# PSocC_Motor_Driver_Design_1.net
KiCad netlist of a schematic drawn in EAGLE
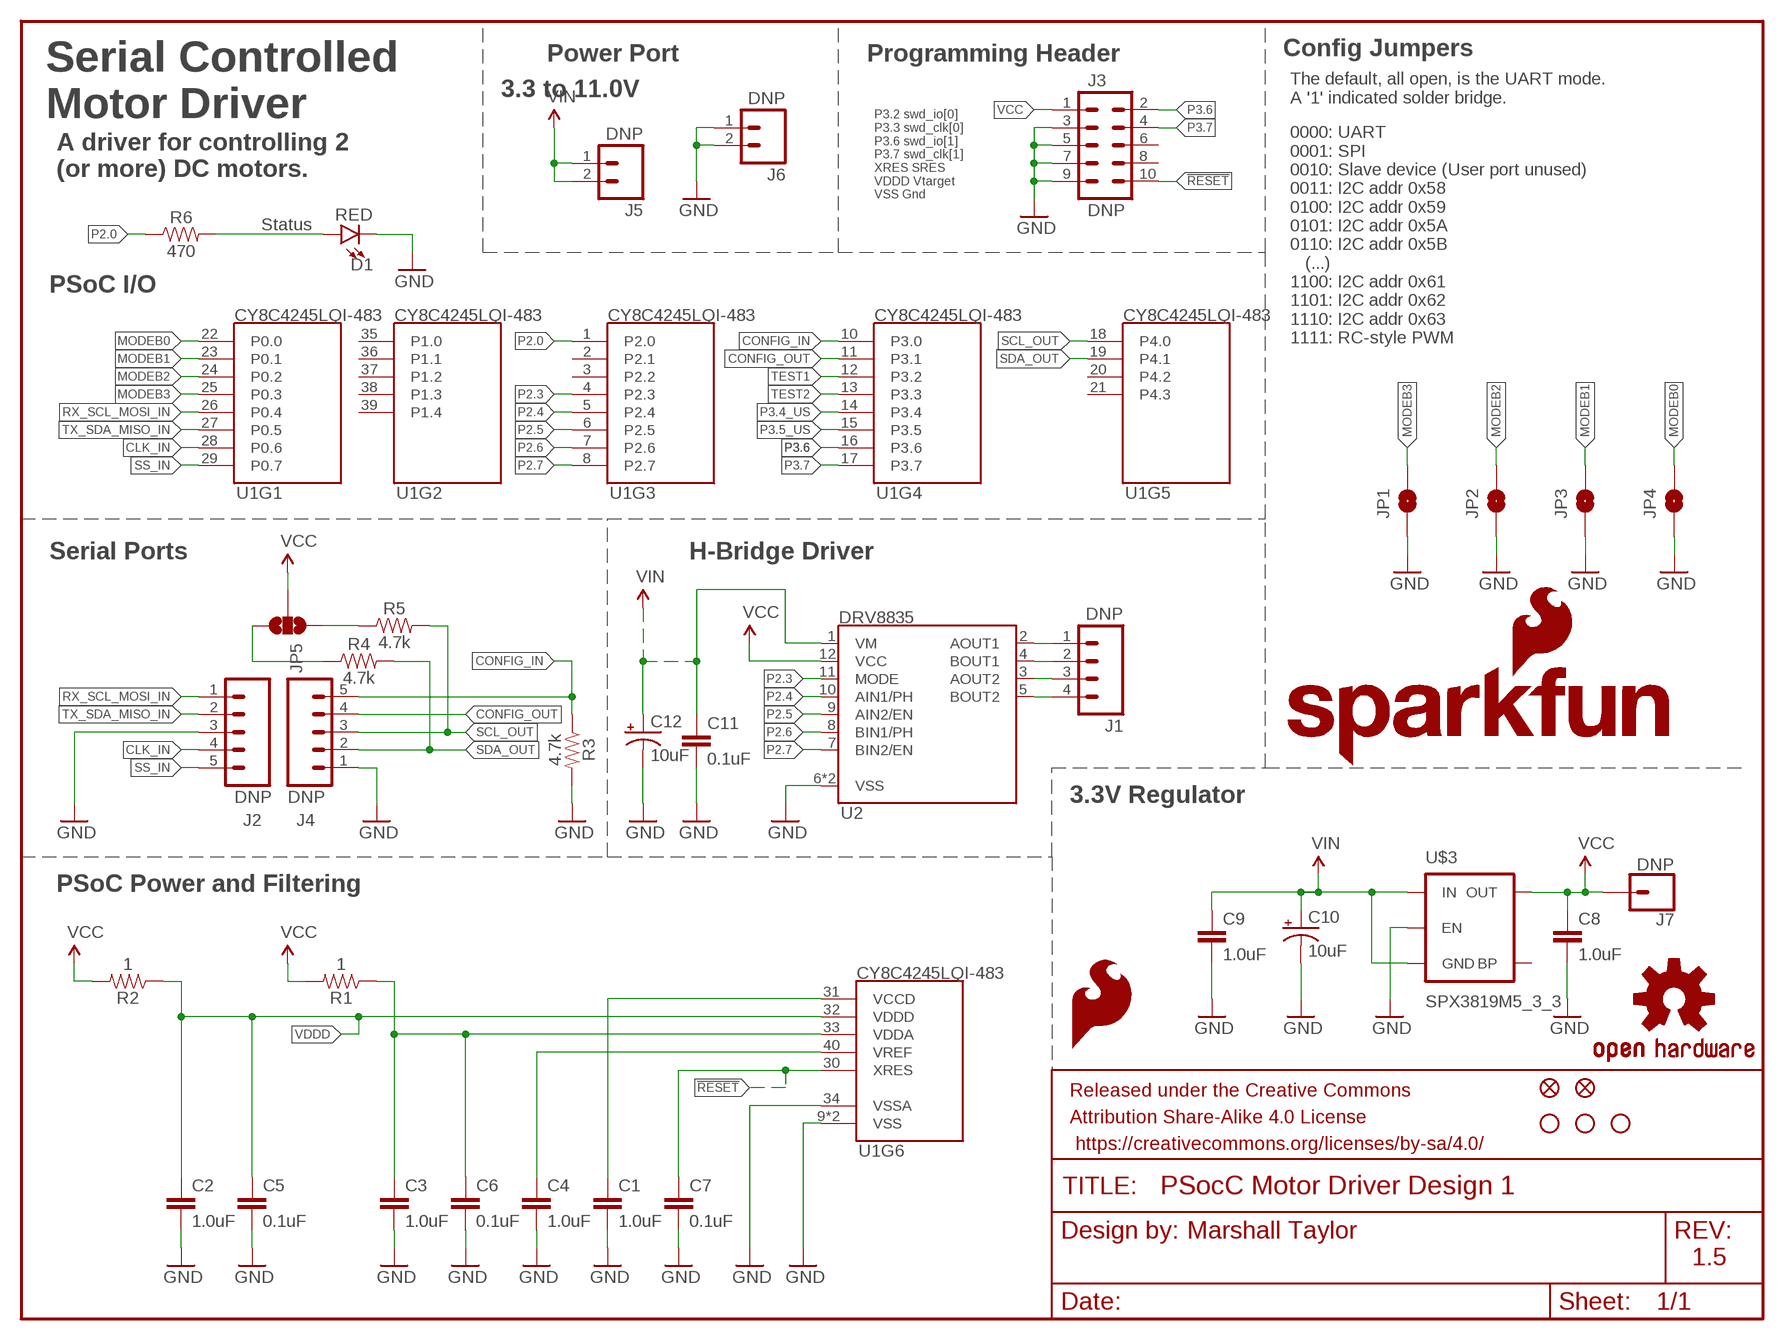
[diagram p0: schematic, sheet 1]

(export (version "E")
  (design (tool "Eeschema 10.0.6"))
  (components
    (comp (ref "C1")
      (value "1.0uF")
      (footprint "eagle-import:0402")
      (libsource (lib "eagle-import") (part "1.0UF-0402-16V-10%"))
    )
    (comp (ref "C2")
      (value "1.0uF")
      (footprint "eagle-import:0402")
      (libsource (lib "eagle-import") (part "1.0UF-0402-16V-10%"))
    )
    (comp (ref "C3")
      (value "1.0uF")
      (footprint "eagle-import:0402")
      (libsource (lib "eagle-import") (part "1.0UF-0402-16V-10%"))
    )
    (comp (ref "C4")
      (value "1.0uF")
      (footprint "eagle-import:0402")
      (libsource (lib "eagle-import") (part "1.0UF-0402-16V-10%"))
    )
    (comp (ref "C5")
      (value "0.1uF")
      (footprint "eagle-import:0402")
      (libsource (lib "eagle-import") (part "0.1UF-0402-16V-10%"))
    )
    (comp (ref "C6")
      (value "0.1uF")
      (footprint "eagle-import:0402")
      (libsource (lib "eagle-import") (part "0.1UF-0402-16V-10%"))
    )
    (comp (ref "C7")
      (value "0.1uF")
      (footprint "eagle-import:0402")
      (libsource (lib "eagle-import") (part "0.1UF-0402-16V-10%"))
    )
    (comp (ref "C8")
      (value "1.0uF")
      (footprint "eagle-import:0402")
      (libsource (lib "eagle-import") (part "1.0UF-0402-16V-10%"))
    )
    (comp (ref "C9")
      (value "1.0uF")
      (footprint "eagle-import:0402")
      (libsource (lib "eagle-import") (part "1.0UF-0402-16V-10%"))
    )
    (comp (ref "C10")
      (value "10uF")
      (footprint "eagle-import:EIA3216")
      (libsource (lib "eagle-import") (part "10UF-POLAR-EIA3216-16V-10%(TANT)"))
    )
    (comp (ref "C11")
      (value "0.1uF")
      (footprint "eagle-import:0402")
      (libsource (lib "eagle-import") (part "0.1UF-0402-16V-10%"))
    )
    (comp (ref "C12")
      (value "10uF")
      (footprint "eagle-import:EIA3216")
      (libsource (lib "eagle-import") (part "10UF-POLAR-EIA3216-16V-10%(TANT)"))
    )
    (comp (ref "D1")
      (value "RED")
      (footprint "eagle-import:LED-0603")
      (libsource (lib "eagle-import") (part "LED-RED0603"))
    )
    (comp (ref "FD1")
      (value "FIDUCIALUFIDUCIAL")
      (footprint "eagle-import:MICRO-FIDUCIAL")
      (libsource (lib "eagle-import") (part "FIDUCIALUFIDUCIAL"))
    )
    (comp (ref "FD2")
      (value "FIDUCIALUFIDUCIAL")
      (footprint "eagle-import:MICRO-FIDUCIAL")
      (libsource (lib "eagle-import") (part "FIDUCIALUFIDUCIAL"))
    )
    (comp (ref "FRAME1")
      (value "FRAME-LETTER")
      (footprint "eagle-import:CREATIVE_COMMONS")
      (libsource (lib "eagle-import") (part "FRAME-LETTER"))
    )
    (comp (ref "H1")
      (value "STAND-OFF")
      (footprint "eagle-import:STAND-OFF")
      (libsource (lib "eagle-import") (part "STAND-OFF"))
    )
    (comp (ref "H2")
      (value "STAND-OFF")
      (footprint "eagle-import:STAND-OFF")
      (libsource (lib "eagle-import") (part "STAND-OFF"))
    )
    (comp (ref "H3")
      (value "STAND-OFF")
      (footprint "eagle-import:STAND-OFF")
      (libsource (lib "eagle-import") (part "STAND-OFF"))
    )
    (comp (ref "J1")
      (value "DNP")
      (footprint "eagle-import:1X04")
      (libsource (lib "eagle-import") (part "M04PTH"))
    )
    (comp (ref "J2")
      (value "DNP")
      (footprint "eagle-import:1X05")
      (libsource (lib "eagle-import") (part "M05PTH"))
    )
    (comp (ref "J3")
      (value "DNP")
      (footprint "eagle-import:2X5_PTH_SILK_.05")
      (libsource (lib "eagle-import") (part "M05X20.05_IN_PTH_SILK"))
    )
    (comp (ref "J4")
      (value "DNP")
      (footprint "eagle-import:1X05")
      (libsource (lib "eagle-import") (part "M05PTH"))
    )
    (comp (ref "J5")
      (value "DNP")
      (footprint "eagle-import:1X02")
      (libsource (lib "eagle-import") (part "M02PTH"))
    )
    (comp (ref "J6")
      (value "DNP")
      (footprint "eagle-import:1X02")
      (libsource (lib "eagle-import") (part "M02PTH"))
    )
    (comp (ref "J7")
      (value "DNP")
      (footprint "eagle-import:1X01")
      (libsource (lib "eagle-import") (part "CONN_01PTH"))
    )
    (comp (ref "JP1")
      (value "JUMPER-PAD-2")
      (footprint "eagle-import:PAD-JUMPER-2-NO_YES_SILK")
      (libsource (lib "eagle-import") (part "JUMPER-PAD-2-NOYES_SILK"))
    )
    (comp (ref "JP2")
      (value "JUMPER-PAD-2")
      (footprint "eagle-import:PAD-JUMPER-2-NO_YES_SILK")
      (libsource (lib "eagle-import") (part "JUMPER-PAD-2-NOYES_SILK"))
    )
    (comp (ref "JP3")
      (value "JUMPER-PAD-2")
      (footprint "eagle-import:PAD-JUMPER-2-NO_YES_SILK")
      (libsource (lib "eagle-import") (part "JUMPER-PAD-2-NOYES_SILK"))
    )
    (comp (ref "JP4")
      (value "JUMPER-PAD-2")
      (footprint "eagle-import:PAD-JUMPER-2-NO_YES_SILK")
      (libsource (lib "eagle-import") (part "JUMPER-PAD-2-NOYES_SILK"))
    )
    (comp (ref "JP5")
      (value "JUMPER-PAD-3-NOYES_SILK")
      (footprint "eagle-import:PAD-JUMPER-3-NO_YES_SILK")
      (libsource (lib "eagle-import") (part "JUMPER-PAD-3-NOYES_SILK"))
    )
    (comp (ref "LOGO1")
      (value "SFE_LOGO_FLAME.1_INCH")
      (footprint "eagle-import:SFE_LOGO_FLAME_.1")
      (libsource (lib "eagle-import") (part "SFE_LOGO_FLAME.1_INCH"))
    )
    (comp (ref "LOGO2")
      (value "OSHW-LOGOMINI")
      (footprint "eagle-import:OSHW-LOGO-MINI")
      (libsource (lib "eagle-import") (part "OSHW-LOGOMINI"))
    )
    (comp (ref "LOGO3")
      (value "SFE_LOGO_NAME_FLAME.1_INCH")
      (footprint "eagle-import:SFE_LOGO_NAME_FLAME_.1")
      (libsource (lib "eagle-import") (part "SFE_LOGO_NAME_FLAME.1_INCH"))
    )
    (comp (ref "R1")
      (value "1")
      (footprint "eagle-import:0603")
      (libsource (lib "eagle-import") (part "1OHM-0603-1/10W-1%"))
    )
    (comp (ref "R2")
      (value "1")
      (footprint "eagle-import:0603")
      (libsource (lib "eagle-import") (part "1OHM-0603-1/10W-1%"))
    )
    (comp (ref "R3")
      (value "4.7k")
      (footprint "eagle-import:0603")
      (libsource (lib "eagle-import") (part "4.7KOHM-0603-1/10W-1%"))
    )
    (comp (ref "R4")
      (value "4.7k")
      (footprint "eagle-import:0603")
      (libsource (lib "eagle-import") (part "4.7KOHM-0603-1/10W-1%"))
    )
    (comp (ref "R5")
      (value "4.7k")
      (footprint "eagle-import:0603")
      (libsource (lib "eagle-import") (part "4.7KOHM-0603-1/10W-1%"))
    )
    (comp (ref "R6")
      (value "470")
      (footprint "eagle-import:0603")
      (libsource (lib "eagle-import") (part "470OHM-0603-1/10W-1%"))
    )
    (comp (ref "U$3")
      (value "SPX3819M5_3_3")
      (footprint "eagle-import:SOT-23-5-VREG")
      (libsource (lib "eagle-import") (part "SPX3819"))
    )
    (comp (ref "U1")
      (value "CY8C4245LQI-483")
      (footprint "eagle-import:QFN-40")
      (libsource (lib "eagle-import") (part "CY8C4245LQI"))
    )
    (comp (ref "U2")
      (value "DRV8835")
      (footprint "eagle-import:WSON-12")
      (fields (field (name "PROD_ID") "IC-13342"))
      (libsource (lib "eagle-import") (part "DRV883X"))
    )
  )
  (nets
    (net (code "1") (name "/~{RESET}") (class "Default")
      (node (ref "C7") (pin "1") (pinfunction "1_1") (pintype "passive"))
      (node (ref "J3") (pin "10") (pinfunction "10_10") (pintype "passive"))
      (node (ref "U1") (pin "30") (pinfunction "XRES_30") (pintype "bidirectional"))
    )
    (net (code "2") (name "CLK_IN") (class "Default")
      (node (ref "J2") (pin "4") (pinfunction "4_4") (pintype "passive"))
      (node (ref "U1") (pin "28") (pinfunction "P0.6_28") (pintype "bidirectional"))
    )
    (net (code "3") (name "CONFIG_IN") (class "Default")
      (node (ref "J4") (pin "5") (pinfunction "5_5") (pintype "passive"))
      (node (ref "R3") (pin "1") (pinfunction "1_1") (pintype "passive"))
      (node (ref "U1") (pin "10") (pinfunction "P3.0_10") (pintype "bidirectional"))
    )
    (net (code "4") (name "CONFIG_OUT") (class "Default")
      (node (ref "J4") (pin "4") (pinfunction "4_4") (pintype "passive"))
      (node (ref "U1") (pin "11") (pinfunction "P3.1_11") (pintype "bidirectional"))
    )
    (net (code "5") (name "GND") (class "Default")
      (node (ref "C1") (pin "2") (pinfunction "2_2") (pintype "passive"))
      (node (ref "C10") (pin "-") (pinfunction "-_-") (pintype "passive"))
      (node (ref "C11") (pin "2") (pinfunction "2_2") (pintype "passive"))
      (node (ref "C12") (pin "-") (pinfunction "-_-") (pintype "passive"))
      (node (ref "C2") (pin "2") (pinfunction "2_2") (pintype "passive"))
      (node (ref "C3") (pin "2") (pinfunction "2_2") (pintype "passive"))
      (node (ref "C4") (pin "2") (pinfunction "2_2") (pintype "passive"))
      (node (ref "C5") (pin "2") (pinfunction "2_2") (pintype "passive"))
      (node (ref "C6") (pin "2") (pinfunction "2_2") (pintype "passive"))
      (node (ref "C7") (pin "2") (pinfunction "2_2") (pintype "passive"))
      (node (ref "C8") (pin "2") (pinfunction "2_2") (pintype "passive"))
      (node (ref "C9") (pin "2") (pinfunction "2_2") (pintype "passive"))
      (node (ref "D1") (pin "C") (pinfunction "C_C") (pintype "passive"))
      (node (ref "J2") (pin "3") (pinfunction "3_3") (pintype "passive"))
      (node (ref "J3") (pin "3") (pinfunction "3_3") (pintype "passive"))
      (node (ref "J3") (pin "5") (pinfunction "5_5") (pintype "passive"))
      (node (ref "J3") (pin "7") (pinfunction "7_7") (pintype "passive"))
      (node (ref "J3") (pin "9") (pinfunction "9_9") (pintype "passive"))
      (node (ref "J4") (pin "1") (pinfunction "1_1") (pintype "passive"))
      (node (ref "J6") (pin "1") (pinfunction "1_1") (pintype "passive"))
      (node (ref "J6") (pin "2") (pinfunction "2_2") (pintype "passive"))
      (node (ref "JP1") (pin "1") (pinfunction "1_1") (pintype "passive"))
      (node (ref "JP2") (pin "1") (pinfunction "1_1") (pintype "passive"))
      (node (ref "JP3") (pin "1") (pinfunction "1_1") (pintype "passive"))
      (node (ref "JP4") (pin "1") (pinfunction "1_1") (pintype "passive"))
      (node (ref "R3") (pin "2") (pinfunction "2_2") (pintype "passive"))
      (node (ref "U$3") (pin "3") (pinfunction "EN_3") (pintype "input"))
      (node (ref "U1") (pin "34") (pinfunction "VSSA_34") (pintype "bidirectional"))
      (node (ref "U1") (pin "9") (pinfunction "VSS_9") (pintype "bidirectional"))
      (node (ref "U1") (pin "EP") (pinfunction "VSS_EP") (pintype "bidirectional"))
      (node (ref "U2") (pin "6") (pinfunction "VSS_6") (pintype "bidirectional"))
      (node (ref "U2") (pin "PAD") (pinfunction "VSS_PAD") (pintype "bidirectional"))
    )
    (net (code "6") (name "MODEB0") (class "Default")
      (node (ref "JP4") (pin "2") (pinfunction "2_2") (pintype "passive"))
      (node (ref "U1") (pin "22") (pinfunction "P0.0_22") (pintype "bidirectional"))
    )
    (net (code "7") (name "MODEB1") (class "Default")
      (node (ref "JP3") (pin "2") (pinfunction "2_2") (pintype "passive"))
      (node (ref "U1") (pin "23") (pinfunction "P0.1_23") (pintype "bidirectional"))
    )
    (net (code "8") (name "MODEB2") (class "Default")
      (node (ref "JP2") (pin "2") (pinfunction "2_2") (pintype "passive"))
      (node (ref "U1") (pin "24") (pinfunction "P0.2_24") (pintype "bidirectional"))
    )
    (net (code "9") (name "MODEB3") (class "Default")
      (node (ref "JP1") (pin "2") (pinfunction "2_2") (pintype "passive"))
      (node (ref "U1") (pin "25") (pinfunction "P0.3_25") (pintype "bidirectional"))
    )
    (net (code "10") (name "Net-(D1-PadA)") (class "Default")
      (node (ref "D1") (pin "A") (pinfunction "A_A") (pintype "passive"))
      (node (ref "R6") (pin "2") (pinfunction "2_2") (pintype "passive"))
    )
    (net (code "11") (name "Net-(JP5-Pad1)") (class "Default")
      (node (ref "JP5") (pin "1") (pinfunction "1_1") (pintype "passive"))
      (node (ref "R5") (pin "1") (pinfunction "1_1") (pintype "passive"))
    )
    (net (code "12") (name "Net-(JP5-Pad3)") (class "Default")
      (node (ref "JP5") (pin "3") (pinfunction "3_3") (pintype "passive"))
      (node (ref "R4") (pin "1") (pinfunction "1_1") (pintype "passive"))
    )
    (net (code "13") (name "Net-(U1F-VCCD)") (class "Default")
      (node (ref "C1") (pin "1") (pinfunction "1_1") (pintype "passive"))
      (node (ref "U1") (pin "31") (pinfunction "VCCD_31") (pintype "bidirectional"))
    )
    (net (code "14") (name "Net-(U1F-VDDA)") (class "Default")
      (node (ref "C3") (pin "1") (pinfunction "1_1") (pintype "passive"))
      (node (ref "C6") (pin "1") (pinfunction "1_1") (pintype "passive"))
      (node (ref "R1") (pin "1") (pinfunction "1_1") (pintype "passive"))
      (node (ref "U1") (pin "33") (pinfunction "VDDA_33") (pintype "bidirectional"))
    )
    (net (code "15") (name "Net-(U1F-VREF)") (class "Default")
      (node (ref "C4") (pin "1") (pinfunction "1_1") (pintype "passive"))
      (node (ref "U1") (pin "40") (pinfunction "VREF_40") (pintype "bidirectional"))
    )
    (net (code "16") (name "Net-(U2-AOUT1)") (class "Default")
      (node (ref "J1") (pin "1") (pinfunction "1_1") (pintype "passive"))
      (node (ref "U2") (pin "2") (pinfunction "AOUT1_2") (pintype "bidirectional"))
    )
    (net (code "17") (name "Net-(U2-AOUT2)") (class "Default")
      (node (ref "J1") (pin "3") (pinfunction "3_3") (pintype "passive"))
      (node (ref "U2") (pin "3") (pinfunction "AOUT2_3") (pintype "bidirectional"))
    )
    (net (code "18") (name "Net-(U2-BOUT1)") (class "Default")
      (node (ref "J1") (pin "2") (pinfunction "2_2") (pintype "passive"))
      (node (ref "U2") (pin "4") (pinfunction "BOUT1_4") (pintype "bidirectional"))
    )
    (net (code "19") (name "Net-(U2-BOUT2)") (class "Default")
      (node (ref "J1") (pin "4") (pinfunction "4_4") (pintype "passive"))
      (node (ref "U2") (pin "5") (pinfunction "BOUT2_5") (pintype "bidirectional"))
    )
    (net (code "20") (name "P2.0") (class "Default")
      (node (ref "R6") (pin "1") (pinfunction "1_1") (pintype "passive"))
      (node (ref "U1") (pin "1") (pinfunction "P2.0_1") (pintype "bidirectional"))
    )
    (net (code "21") (name "P2.3") (class "Default")
      (node (ref "U1") (pin "4") (pinfunction "P2.3_4") (pintype "bidirectional"))
      (node (ref "U2") (pin "11") (pinfunction "MODE_11") (pintype "bidirectional"))
    )
    (net (code "22") (name "P2.4") (class "Default")
      (node (ref "U1") (pin "5") (pinfunction "P2.4_5") (pintype "bidirectional"))
      (node (ref "U2") (pin "10") (pinfunction "AIN1/PH_10") (pintype "bidirectional"))
    )
    (net (code "23") (name "P2.5") (class "Default")
      (node (ref "U1") (pin "6") (pinfunction "P2.5_6") (pintype "bidirectional"))
      (node (ref "U2") (pin "9") (pinfunction "AIN2/EN_9") (pintype "bidirectional"))
    )
    (net (code "24") (name "P2.6") (class "Default")
      (node (ref "U1") (pin "7") (pinfunction "P2.6_7") (pintype "bidirectional"))
      (node (ref "U2") (pin "8") (pinfunction "BIN1/PH_8") (pintype "bidirectional"))
    )
    (net (code "25") (name "P2.7") (class "Default")
      (node (ref "U1") (pin "8") (pinfunction "P2.7_8") (pintype "bidirectional"))
      (node (ref "U2") (pin "7") (pinfunction "BIN2/EN_7") (pintype "bidirectional"))
    )
    (net (code "26") (name "P3.4_US") (class "Default")
      (node (ref "U1") (pin "14") (pinfunction "P3.4_14") (pintype "bidirectional"))
    )
    (net (code "27") (name "P3.5_US") (class "Default")
      (node (ref "U1") (pin "15") (pinfunction "P3.5_15") (pintype "bidirectional"))
    )
    (net (code "28") (name "P3.6") (class "Default")
      (node (ref "J3") (pin "2") (pinfunction "2_2") (pintype "passive"))
      (node (ref "U1") (pin "16") (pinfunction "P3.6_16") (pintype "bidirectional"))
    )
    (net (code "29") (name "P3.7") (class "Default")
      (node (ref "J3") (pin "4") (pinfunction "4_4") (pintype "passive"))
      (node (ref "U1") (pin "17") (pinfunction "P3.7_17") (pintype "bidirectional"))
    )
    (net (code "30") (name "RX_SCL_MOSI_IN") (class "Default")
      (node (ref "J2") (pin "1") (pinfunction "1_1") (pintype "passive"))
      (node (ref "U1") (pin "26") (pinfunction "P0.4_26") (pintype "bidirectional"))
    )
    (net (code "31") (name "SCL_OUT") (class "Default")
      (node (ref "J4") (pin "3") (pinfunction "3_3") (pintype "passive"))
      (node (ref "R5") (pin "2") (pinfunction "2_2") (pintype "passive"))
      (node (ref "U1") (pin "18") (pinfunction "P4.0_18") (pintype "bidirectional"))
    )
    (net (code "32") (name "SDA_OUT") (class "Default")
      (node (ref "J4") (pin "2") (pinfunction "2_2") (pintype "passive"))
      (node (ref "R4") (pin "2") (pinfunction "2_2") (pintype "passive"))
      (node (ref "U1") (pin "19") (pinfunction "P4.1_19") (pintype "bidirectional"))
    )
    (net (code "33") (name "SS_IN") (class "Default")
      (node (ref "J2") (pin "5") (pinfunction "5_5") (pintype "passive"))
      (node (ref "U1") (pin "29") (pinfunction "P0.7_29") (pintype "bidirectional"))
    )
    (net (code "34") (name "TEST1") (class "Default")
      (node (ref "U1") (pin "12") (pinfunction "P3.2_12") (pintype "bidirectional"))
    )
    (net (code "35") (name "TEST2") (class "Default")
      (node (ref "U1") (pin "13") (pinfunction "P3.3_13") (pintype "bidirectional"))
    )
    (net (code "36") (name "TX_SDA_MISO_IN") (class "Default")
      (node (ref "J2") (pin "2") (pinfunction "2_2") (pintype "passive"))
      (node (ref "U1") (pin "27") (pinfunction "P0.5_27") (pintype "bidirectional"))
    )
    (net (code "37") (name "VCC") (class "Default")
      (node (ref "C8") (pin "1") (pinfunction "1_1") (pintype "passive"))
      (node (ref "J3") (pin "1") (pinfunction "1_1") (pintype "passive"))
      (node (ref "J7") (pin "1") (pinfunction "1_1") (pintype "passive"))
      (node (ref "JP5") (pin "2") (pinfunction "2_2") (pintype "passive"))
      (node (ref "R1") (pin "2") (pinfunction "2_2") (pintype "passive"))
      (node (ref "R2") (pin "2") (pinfunction "2_2") (pintype "passive"))
      (node (ref "U$3") (pin "5") (pinfunction "OUT_5") (pintype "passive"))
      (node (ref "U2") (pin "12") (pinfunction "VCC_12") (pintype "bidirectional"))
    )
    (net (code "38") (name "VDDD") (class "Default")
      (node (ref "C2") (pin "1") (pinfunction "1_1") (pintype "passive"))
      (node (ref "C5") (pin "1") (pinfunction "1_1") (pintype "passive"))
      (node (ref "R2") (pin "1") (pinfunction "1_1") (pintype "passive"))
      (node (ref "U1") (pin "32") (pinfunction "VDDD_32") (pintype "bidirectional"))
    )
    (net (code "39") (name "VIN") (class "Default")
      (node (ref "C10") (pin "+") (pinfunction "+_+") (pintype "passive"))
      (node (ref "C11") (pin "1") (pinfunction "1_1") (pintype "passive"))
      (node (ref "C12") (pin "+") (pinfunction "+_+") (pintype "passive"))
      (node (ref "C9") (pin "1") (pinfunction "1_1") (pintype "passive"))
      (node (ref "J5") (pin "1") (pinfunction "1_1") (pintype "passive"))
      (node (ref "J5") (pin "2") (pinfunction "2_2") (pintype "passive"))
      (node (ref "U$3") (pin "1") (pinfunction "IN_1") (pintype "input"))
      (node (ref "U$3") (pin "2") (pinfunction "GND_2") (pintype "input"))
      (node (ref "U2") (pin "1") (pinfunction "VM_1") (pintype "bidirectional"))
    )
    (net (code "40") (name "unconnected-(J3-Pad6)") (class "Default")
      (node (ref "J3") (pin "6") (pinfunction "6_6") (pintype "passive"))
    )
    (net (code "41") (name "unconnected-(J3-Pad8)") (class "Default")
      (node (ref "J3") (pin "8") (pinfunction "8_8") (pintype "passive"))
    )
    (net (code "42") (name "unconnected-(U$3-BP-Pad4)") (class "Default")
      (node (ref "U$3") (pin "4") (pinfunction "BP_4") (pintype "input"))
    )
    (net (code "43") (name "unconnected-(U1B-P1.0-Pad35)") (class "Default")
      (node (ref "U1") (pin "35") (pinfunction "P1.0_35") (pintype "bidirectional"))
    )
    (net (code "44") (name "unconnected-(U1B-P1.1-Pad36)") (class "Default")
      (node (ref "U1") (pin "36") (pinfunction "P1.1_36") (pintype "bidirectional"))
    )
    (net (code "45") (name "unconnected-(U1B-P1.2-Pad37)") (class "Default")
      (node (ref "U1") (pin "37") (pinfunction "P1.2_37") (pintype "bidirectional"))
    )
    (net (code "46") (name "unconnected-(U1B-P1.3-Pad38)") (class "Default")
      (node (ref "U1") (pin "38") (pinfunction "P1.3_38") (pintype "bidirectional"))
    )
    (net (code "47") (name "unconnected-(U1B-P1.4-Pad39)") (class "Default")
      (node (ref "U1") (pin "39") (pinfunction "P1.4_39") (pintype "bidirectional"))
    )
    (net (code "48") (name "unconnected-(U1C-P2.1-Pad2)") (class "Default")
      (node (ref "U1") (pin "2") (pinfunction "P2.1_2") (pintype "bidirectional"))
    )
    (net (code "49") (name "unconnected-(U1C-P2.2-Pad3)") (class "Default")
      (node (ref "U1") (pin "3") (pinfunction "P2.2_3") (pintype "bidirectional"))
    )
    (net (code "50") (name "unconnected-(U1E-P4.2-Pad20)") (class "Default")
      (node (ref "U1") (pin "20") (pinfunction "P4.2_20") (pintype "bidirectional"))
    )
    (net (code "51") (name "unconnected-(U1E-P4.3-Pad21)") (class "Default")
      (node (ref "U1") (pin "21") (pinfunction "P4.3_21") (pintype "bidirectional"))
    )
  )
)
